# Outputs.net
KiCad netlist of a schematic drawn in Altium Designer
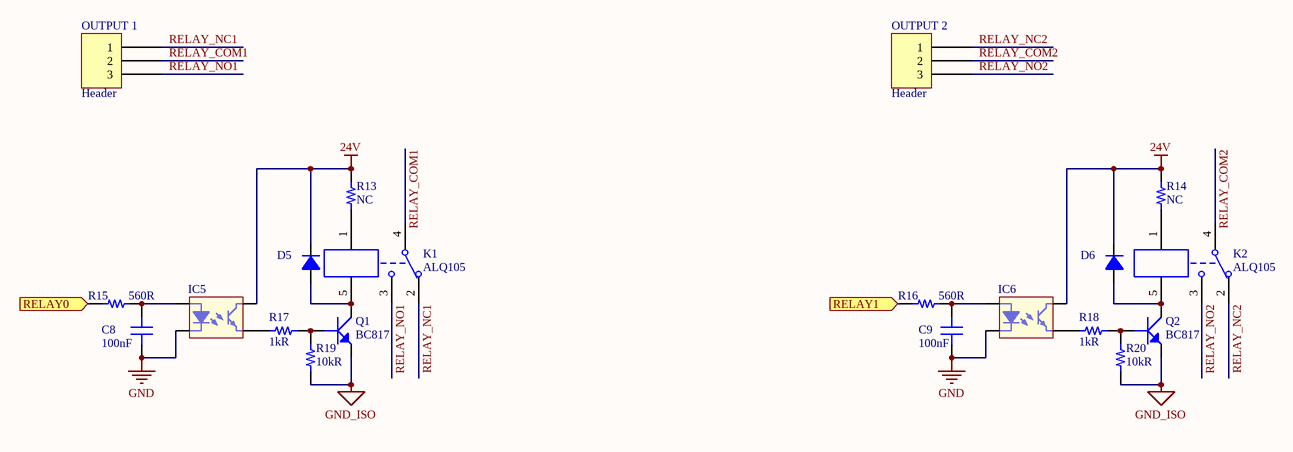
[diagram p0: Outputs.SchDoc]

(export (version "E")
  (design (tool "Eeschema 10.0.6"))
  (components
    (comp (ref "C8")
      (value "100nF")
      (footprint "CAP 0603/1608")
      (description "Ceramic, SMT Capacitor")
      (fields
        (field (name "MANUFACTURER") "Samsung")
        (field (name "MANUFACTURER PART NUMBER") "CL10B104JB8NNNC")
      )
      (libsource (lib "yildizIoT Library") (part "Capacitor - Ceramic"))
    )
    (comp (ref "C9")
      (value "100nF")
      (footprint "CAP 0603/1608")
      (description "Ceramic, SMT Capacitor")
      (fields
        (field (name "MANUFACTURER") "Samsung")
        (field (name "MANUFACTURER PART NUMBER") "CL10B104JB8NNNC")
      )
      (libsource (lib "yildizIoT Library") (part "Capacitor - Ceramic"))
    )
    (comp (ref "D5")
      (value "1N4148WTR")
      (footprint "sod123")
      (description "Diode")
      (fields (field (name "MANUFACTURER") "SMC"))
      (libsource (lib "Muhammet_All_In_One") (part "Diode"))
    )
    (comp (ref "D6")
      (value "1N4148WTR")
      (footprint "sod123")
      (description "Diode")
      (fields (field (name "MANUFACTURER") "SMC"))
      (libsource (lib "Muhammet_All_In_One") (part "Diode"))
    )
    (comp (ref "IC5")
      (value "EL3H7(B)(TA)-VG")
      (footprint "EL3H7-VG")
      (fields (field (name "MANUFACTURER") "Everlight"))
      (libsource (lib "yildizIoT Library") (part "Optoisolator"))
    )
    (comp (ref "IC6")
      (value "EL3H7(B)(TA)-VG")
      (footprint "EL3H7-VG")
      (fields (field (name "MANUFACTURER") "Everlight"))
      (libsource (lib "yildizIoT Library") (part "Optoisolator"))
    )
    (comp (ref "K1")
      (value "ALQ105")
      (footprint "ALQ105")
      (description "Relay or Contactor")
      (fields (field (name "MANUFACTURER") "Panasonic"))
      (libsource (lib "yildizIoT Library") (part "Relay SPDT"))
    )
    (comp (ref "K2")
      (value "ALQ105")
      (footprint "ALQ105")
      (description "Relay or Contactor")
      (fields (field (name "MANUFACTURER") "Panasonic"))
      (libsource (lib "yildizIoT Library") (part "Relay SPDT"))
    )
    (comp (ref "OUTPUT 1")
      (value "Header")
      (footprint "TE 282834-3")
      (fields
        (field (name "MANUFACTURER") "On-Shore Technology")
        (field (name "MANUFACTURER PART NUMBER") "OSTVN03A150")
        (field (name "VOLTAGE") "125V")
      )
      (libsource (lib "yildizIoT Library") (part "3 Pin"))
    )
    (comp (ref "OUTPUT 2")
      (value "Header")
      (footprint "TE 282834-3")
      (fields
        (field (name "MANUFACTURER") "On-Shore Technology")
        (field (name "MANUFACTURER PART NUMBER") "OSTVN03A150")
        (field (name "VOLTAGE") "125V")
      )
      (libsource (lib "yildizIoT Library") (part "3 Pin"))
    )
    (comp (ref "Q1")
      (value "BC817")
      (footprint "SOT23-3")
      (description "Transistor, BC817")
      (fields
        (field (name "MANUFACTURER") "ON Semiconductor")
        (field (name "MANUFACTURER PART NUMBER") "BC817-16LT1G")
      )
      (libsource (lib "MuhammetLib") (part "BC817"))
    )
    (comp (ref "Q2")
      (value "BC817")
      (footprint "SOT23-3")
      (description "Transistor, BC817")
      (fields
        (field (name "MANUFACTURER") "ON Semiconductor")
        (field (name "MANUFACTURER PART NUMBER") "BC817-16LT1G")
      )
      (libsource (lib "MuhammetLib") (part "BC817"))
    )
    (comp (ref "R13")
      (value "NC")
      (footprint "RES 0603/1608")
      (description "Ceramic, SMT Capacitor")
      (libsource (lib "yildizIoT Library") (part "Resistor_Chip"))
    )
    (comp (ref "R14")
      (value "NC")
      (footprint "RES 0603/1608")
      (description "Ceramic, SMT Capacitor")
      (libsource (lib "yildizIoT Library") (part "Resistor_Chip"))
    )
    (comp (ref "R15")
      (value "560R")
      (footprint "RES 0603/1608")
      (description "Ceramic, SMT Capacitor")
      (fields (field (name "MANUFACTURER") "Rohm") (field (name "MANUFACTURER PART NUMBER") "ESR03EZPJ561"))
      (libsource (lib "") (part "Resistor_Chip_1"))
    )
    (comp (ref "R16")
      (value "560R")
      (footprint "RES 0603/1608")
      (description "Ceramic, SMT Capacitor")
      (fields (field (name "MANUFACTURER") "Rohm") (field (name "MANUFACTURER PART NUMBER") "ESR03EZPJ561"))
      (libsource (lib "") (part "Resistor_Chip_1"))
    )
    (comp (ref "R17")
      (value "1kR")
      (footprint "RES 0603/1608")
      (description "Ceramic, SMT Capacitor")
      (fields (field (name "MANUFACTURER") "Rohm") (field (name "MANUFACTURER PART NUMBER") "ESR03EZPJ102"))
      (libsource (lib "yildizIoT Library") (part "Resistor_Chip"))
    )
    (comp (ref "R18")
      (value "1kR")
      (footprint "RES 0603/1608")
      (description "Ceramic, SMT Capacitor")
      (fields (field (name "MANUFACTURER") "Rohm") (field (name "MANUFACTURER PART NUMBER") "ESR03EZPJ102"))
      (libsource (lib "yildizIoT Library") (part "Resistor_Chip"))
    )
    (comp (ref "R19")
      (value "10kR")
      (footprint "RES 0603/1608")
      (description "Ceramic, SMT Capacitor")
      (fields
        (field (name "MANUFACTURER") "Stackpole Electronics")
        (field (name "MANUFACTURER PART NUMBER") "RNCP0603FTD10K0")
      )
      (libsource (lib "yildizIoT Library") (part "Resistor_Chip"))
    )
    (comp (ref "R20")
      (value "10kR")
      (footprint "RES 0603/1608")
      (description "Ceramic, SMT Capacitor")
      (fields
        (field (name "MANUFACTURER") "Stackpole Electronics")
        (field (name "MANUFACTURER PART NUMBER") "RNCP0603FTD10K0")
      )
      (libsource (lib "yildizIoT Library") (part "Resistor_Chip"))
    )
  )
  (nets
    (net (code "1") (name "/RELAY0") (class "Default")
      (node (ref "R15") (pin "1") (pinfunction "1_1") (pintype "passive"))
    )
    (net (code "2") (name "/RELAY1") (class "Default")
      (node (ref "R16") (pin "1") (pinfunction "1_1") (pintype "passive"))
    )
    (net (code "3") (name "/RELAY_COM1") (class "Default")
      (node (ref "K1") (pin "4") (pinfunction "COM_4") (pintype "passive"))
      (node (ref "OUTPUT 1") (pin "2") (pinfunction "2_2") (pintype "passive"))
    )
    (net (code "4") (name "/RELAY_COM2") (class "Default")
      (node (ref "K2") (pin "4") (pinfunction "COM_4") (pintype "passive"))
      (node (ref "OUTPUT 2") (pin "2") (pinfunction "2_2") (pintype "passive"))
    )
    (net (code "5") (name "/RELAY_NC1") (class "Default")
      (node (ref "K1") (pin "2") (pinfunction "NC_2") (pintype "passive"))
      (node (ref "OUTPUT 1") (pin "1") (pinfunction "1_1") (pintype "passive"))
    )
    (net (code "6") (name "/RELAY_NC2") (class "Default")
      (node (ref "K2") (pin "2") (pinfunction "NC_2") (pintype "passive"))
      (node (ref "OUTPUT 2") (pin "1") (pinfunction "1_1") (pintype "passive"))
    )
    (net (code "7") (name "/RELAY_NO1") (class "Default")
      (node (ref "K1") (pin "3") (pinfunction "NO_3") (pintype "passive"))
      (node (ref "OUTPUT 1") (pin "3") (pinfunction "3_3") (pintype "passive"))
    )
    (net (code "8") (name "/RELAY_NO2") (class "Default")
      (node (ref "K2") (pin "3") (pinfunction "NO_3") (pintype "passive"))
      (node (ref "OUTPUT 2") (pin "3") (pinfunction "3_3") (pintype "passive"))
    )
    (net (code "9") (name "24V") (class "Default")
      (node (ref "D5") (pin "2") (pinfunction "2_2") (pintype "passive"))
      (node (ref "D6") (pin "2") (pinfunction "2_2") (pintype "passive"))
      (node (ref "IC5") (pin "4") (pinfunction "4_4") (pintype "passive"))
      (node (ref "IC6") (pin "4") (pinfunction "4_4") (pintype "passive"))
      (node (ref "R13") (pin "2") (pinfunction "2_2") (pintype "passive"))
      (node (ref "R14") (pin "2") (pinfunction "2_2") (pintype "passive"))
    )
    (net (code "10") (name "GND") (class "Default")
      (node (ref "C8") (pin "1") (pinfunction "1_1") (pintype "passive"))
      (node (ref "C9") (pin "1") (pinfunction "1_1") (pintype "passive"))
      (node (ref "IC5") (pin "2") (pinfunction "2_2") (pintype "passive"))
      (node (ref "IC6") (pin "2") (pinfunction "2_2") (pintype "passive"))
    )
    (net (code "11") (name "GND_ISO") (class "Default")
      (node (ref "Q1") (pin "2") (pinfunction "E_2") (pintype "passive"))
      (node (ref "Q2") (pin "2") (pinfunction "E_2") (pintype "passive"))
      (node (ref "R19") (pin "2") (pinfunction "2_2") (pintype "passive"))
      (node (ref "R20") (pin "2") (pinfunction "2_2") (pintype "passive"))
    )
    (net (code "12") (name "Net-(C8-Pad2)") (class "Default")
      (node (ref "C8") (pin "2") (pinfunction "2_2") (pintype "passive"))
      (node (ref "IC5") (pin "1") (pinfunction "1_1") (pintype "passive"))
      (node (ref "R15") (pin "2") (pinfunction "2_2") (pintype "passive"))
    )
    (net (code "13") (name "Net-(C9-Pad2)") (class "Default")
      (node (ref "C9") (pin "2") (pinfunction "2_2") (pintype "passive"))
      (node (ref "IC6") (pin "1") (pinfunction "1_1") (pintype "passive"))
      (node (ref "R16") (pin "2") (pinfunction "2_2") (pintype "passive"))
    )
    (net (code "14") (name "Net-(IC5-Pad3)") (class "Default")
      (node (ref "IC5") (pin "3") (pinfunction "3_3") (pintype "passive"))
      (node (ref "R17") (pin "2") (pinfunction "2_2") (pintype "passive"))
    )
    (net (code "15") (name "Net-(IC6-Pad3)") (class "Default")
      (node (ref "IC6") (pin "3") (pinfunction "3_3") (pintype "passive"))
      (node (ref "R18") (pin "2") (pinfunction "2_2") (pintype "passive"))
    )
    (net (code "16") (name "Net-(K1-COIL-Pad1)") (class "Default")
      (node (ref "K1") (pin "1") (pinfunction "COIL_1") (pintype "passive"))
      (node (ref "R13") (pin "1") (pinfunction "1_1") (pintype "passive"))
    )
    (net (code "17") (name "Net-(K2-COIL-Pad1)") (class "Default")
      (node (ref "K2") (pin "1") (pinfunction "COIL_1") (pintype "passive"))
      (node (ref "R14") (pin "1") (pinfunction "1_1") (pintype "passive"))
    )
    (net (code "18") (name "Net-(Q1-B)") (class "Default")
      (node (ref "Q1") (pin "1") (pinfunction "B_1") (pintype "passive"))
      (node (ref "R17") (pin "1") (pinfunction "1_1") (pintype "passive"))
      (node (ref "R19") (pin "1") (pinfunction "1_1") (pintype "passive"))
    )
    (net (code "19") (name "Net-(Q1-C)") (class "Default")
      (node (ref "D5") (pin "1") (pinfunction "1_1") (pintype "passive"))
      (node (ref "K1") (pin "5") (pinfunction "COIL_5") (pintype "passive"))
      (node (ref "Q1") (pin "3") (pinfunction "C_3") (pintype "passive"))
    )
    (net (code "20") (name "Net-(Q2-B)") (class "Default")
      (node (ref "Q2") (pin "1") (pinfunction "B_1") (pintype "passive"))
      (node (ref "R18") (pin "1") (pinfunction "1_1") (pintype "passive"))
      (node (ref "R20") (pin "1") (pinfunction "1_1") (pintype "passive"))
    )
    (net (code "21") (name "Net-(Q2-C)") (class "Default")
      (node (ref "D6") (pin "1") (pinfunction "1_1") (pintype "passive"))
      (node (ref "K2") (pin "5") (pinfunction "COIL_5") (pintype "passive"))
      (node (ref "Q2") (pin "3") (pinfunction "C_3") (pintype "passive"))
    )
  )
)
